# UBC-Thunderbots_PCB_Power__archive_power.net
KiCad netlist of a schematic drawn in Altium Designer
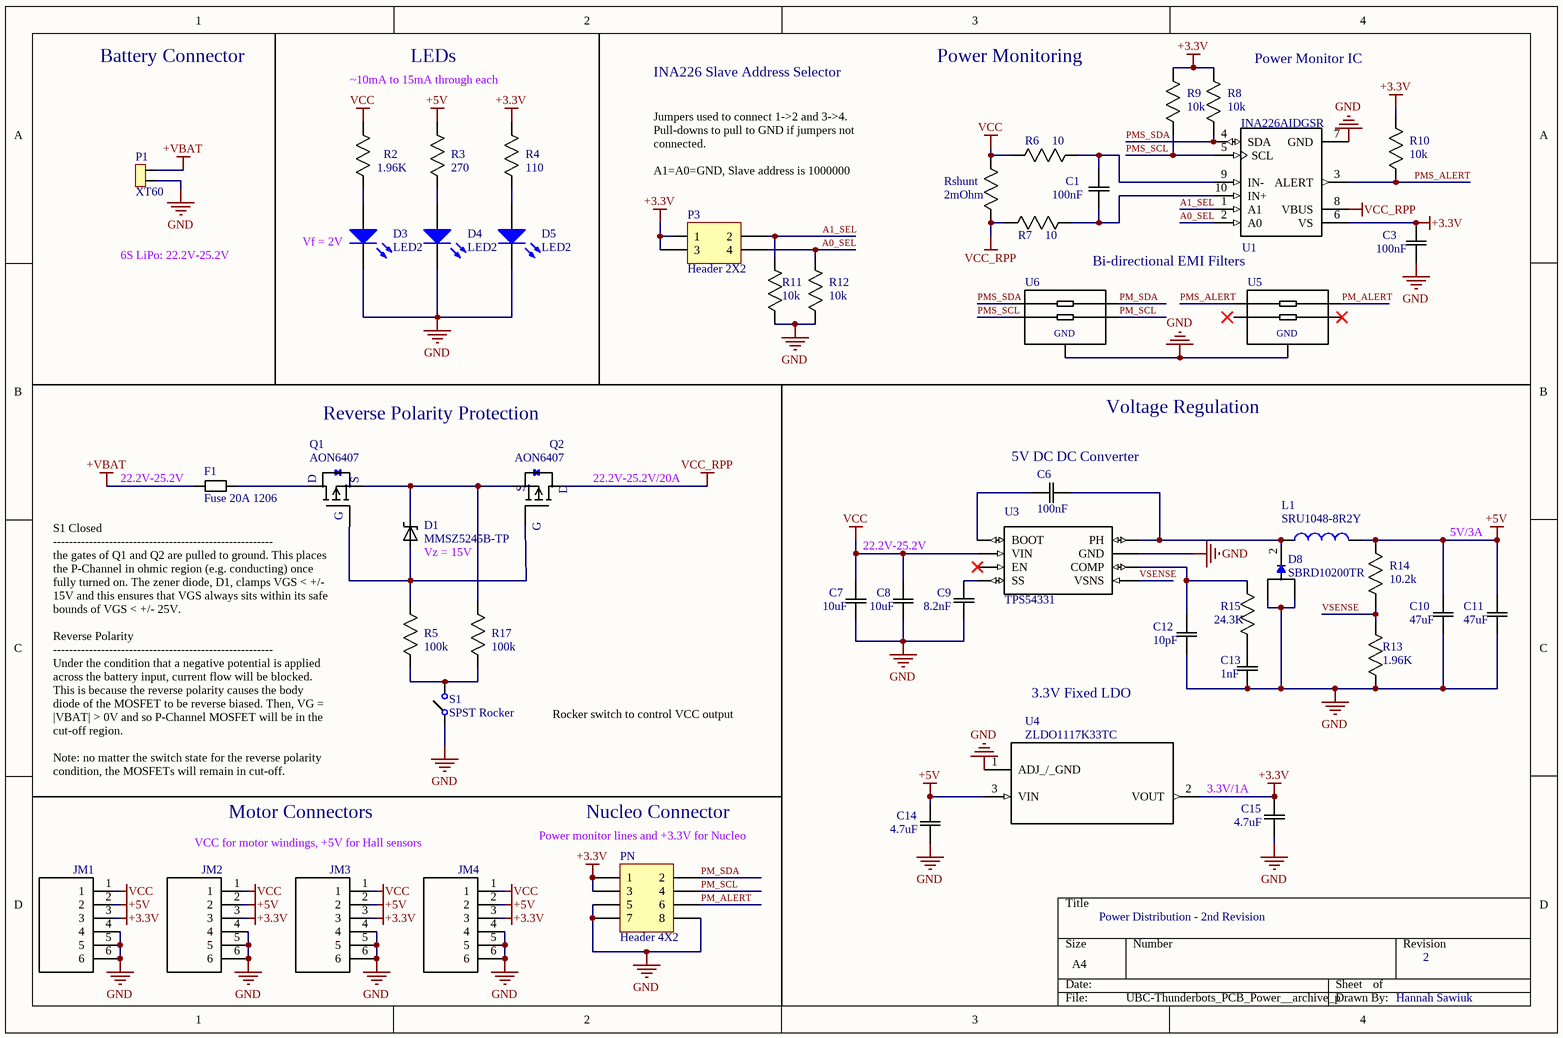
[diagram p0: UBC-Thunderbots_PCB_Power__archive_power-v2.0_pcb__power-v2.0.SchDoc]

(export (version "E")
  (design (tool "Eeschema 10.0.6"))
  (components
    (comp (ref "C1")
      (value "100nF")
      (footprint "0805")
      (description "CAP CER 0.1UF 50V X7R 0805")
      (fields (field (name "MP") "CC0805KRX7R9BB104") (field (name "MF") "Yageo"))
      (libsource (lib "AltiumLibraries") (part "CAP 100nF 0805"))
    )
    (comp (ref "C3")
      (value "100nF")
      (footprint "0805")
      (description "CAP CER 0.1UF 50V X7R 0805")
      (fields (field (name "MP") "CC0805KRX7R9BB104") (field (name "MF") "Yageo"))
      (libsource (lib "AltiumLibraries") (part "CAP 100nF 0805"))
    )
    (comp (ref "C6")
      (value "100nF")
      (footprint "0805")
      (description "CAP CER 0.1UF 50V X7R 0805")
      (fields (field (name "MP") "CC0805KRX7R9BB104") (field (name "MF") "Yageo"))
      (libsource (lib "AltiumLibraries") (part "CAP 100nF 0805"))
    )
    (comp (ref "C7")
      (value "10uF")
      (footprint "1210")
      (description "CAP CER 10UF 50V X7R 1210")
      (fields (field (name "MP") "CL32B106KBJNNWE") (field (name "MF") "Samsung Electro-Mechanics"))
      (libsource (lib "AltiumLibraries") (part "CAP 10uF 1210"))
    )
    (comp (ref "C8")
      (value "10uF")
      (footprint "1210")
      (description "CAP CER 10UF 50V X7R 1210")
      (fields (field (name "MP") "CL32B106KBJNNWE") (field (name "MF") "Samsung Electro-Mechanics"))
      (libsource (lib "AltiumLibraries") (part "CAP 10uF 1210"))
    )
    (comp (ref "C9")
      (value "8.2nF")
      (footprint "0805")
      (description "CAP CER 8200PF 50V X7R 0805")
      (fields (field (name "MP") "C0805C822K5RACTU") (field (name "MF") "KEMET"))
      (libsource (lib "AltiumLibraries") (part "CAP 8.2nF 0805"))
    )
    (comp (ref "C10")
      (value "47uF")
      (footprint "1210")
      (description "CAP CER 47UF 6.3V X7R 1210")
      (fields (field (name "MP") "GCM32ER70J476KE19L") (field (name "MF") "Murata Electronics"))
      (libsource (lib "AltiumLibraries") (part "CAP 47uF 1210"))
    )
    (comp (ref "C11")
      (value "47uF")
      (footprint "1210")
      (description "CAP CER 47UF 6.3V X7R 1210")
      (fields (field (name "MP") "GCM32ER70J476KE19L") (field (name "MF") "Murata Electronics"))
      (libsource (lib "AltiumLibraries") (part "CAP 47uF 1210"))
    )
    (comp (ref "C12")
      (value "10pF")
      (footprint "0603")
      (description "CAP CER SMD 0603 10PF 10% X7R 50")
      (fields (field (name "MP") "C0603C100K5RAC7867") (field (name "MF") "KEMET"))
      (libsource (lib "AltiumLibraries") (part "CAP 10pF 0603"))
    )
    (comp (ref "C13")
      (value "1nF")
      (footprint "0805")
      (description "CAP CER 1000PF 50V X7R 0805")
      (fields (field (name "MP") "CC0805KRX7R9BB102") (field (name "MF") "Yageo"))
      (libsource (lib "AltiumLibraries") (part "CAP 1nF 0805"))
    )
    (comp (ref "C14")
      (value "4.7uF")
      (footprint "0805")
      (description "CAP CER 4.7UF 25V X5R 0805")
      (fields (field (name "MP") "CL21B475KOFNNNE") (field (name "MF") "Samsung Electro-Mechanics"))
      (libsource (lib "AltiumLibraries") (part "CAP 4.7uF 0805"))
    )
    (comp (ref "C15")
      (value "4.7uF")
      (footprint "0805")
      (description "CAP CER 4.7UF 25V X5R 0805")
      (fields (field (name "MP") "CL21B475KOFNNNE") (field (name "MF") "Samsung Electro-Mechanics"))
      (libsource (lib "AltiumLibraries") (part "CAP 4.7uF 0805"))
    )
    (comp (ref "D1")
      (value "MMSZ5245B-TP")
      (footprint "SOD-123")
      (description "Zener Diode 15V 500mW ±5% Surface Mount SOD-123")
      (fields (field (name "MP") "MMSZ5224BT1G") (field (name "MF") "ON Semiconductor"))
      (libsource (lib "AltiumLibraries") (part "MMSZ5245B-TP"))
    )
    (comp (ref "D3")
      (value "LED2")
      (footprint "3.2X1.6X1.1")
      (description "Typical RED, GREEN, YELLOW, AMBER GaAs LED")
      (fields (field (name "MF") "Lite-On Inc.") (field (name "MP") "LTST-C191KGKT"))
      (libsource (lib "AltiumLibraries") (part "LED GREEN SMD"))
    )
    (comp (ref "D4")
      (value "LED2")
      (footprint "3.2X1.6X1.1")
      (description "Typical RED, GREEN, YELLOW, AMBER GaAs LED")
      (fields (field (name "MF") "Lite-On Inc.") (field (name "MP") "LTST-C191KGKT"))
      (libsource (lib "AltiumLibraries") (part "LED GREEN SMD"))
    )
    (comp (ref "D5")
      (value "LED2")
      (footprint "3.2X1.6X1.1")
      (description "Typical RED, GREEN, YELLOW, AMBER GaAs LED")
      (fields (field (name "MF") "Lite-On Inc.") (field (name "MP") "LTST-C191KGKT"))
      (libsource (lib "AltiumLibraries") (part "LED GREEN SMD"))
    )
    (comp (ref "D8")
      (value "SBRD10200TR")
      (footprint "DPAK")
      (description "Diode Schottky 200V 10A Surface Mount DPAK")
      (fields (field (name "MF") "SMC Diode"))
      (libsource (lib "AltiumLibraries") (part "SBRD10200TR"))
    )
    (comp (ref "F1")
      (value "Fuse 20A 1206")
      (footprint "1206")
      (description "FUSE BOARD MOUNT 20A 32VAC 63VDC")
      (fields (field (name "MF") "Schurter Inc.") (field (name "MP") "3413.0331.22"))
      (libsource (lib "AltiumLibraries") (part "Fuse 20A 1206"))
    )
    (comp (ref "JM1")
      (value "CONN HEADER VERT 6POS 3.96MM")
      (footprint "CN HDR 6POS 3.96MM")
      (description "Connector Header Through Hole 6 position 0.156\" (3.96mm)")
      (fields (field (name "MF") "TE Connectivity") (field (name "MP") "1877285-6"))
      (libsource (lib "AltiumLibraries") (part "CONN HEADER VERT 6POS 3.96MM"))
    )
    (comp (ref "JM2")
      (value "CONN HEADER VERT 6POS 3.96MM")
      (footprint "CN HDR 6POS 3.96MM")
      (description "Connector Header Through Hole 6 position 0.156\" (3.96mm)")
      (fields (field (name "MF") "TE Connectivity") (field (name "MP") "1877285-6"))
      (libsource (lib "AltiumLibraries") (part "CONN HEADER VERT 6POS 3.96MM"))
    )
    (comp (ref "JM3")
      (value "CONN HEADER VERT 6POS 3.96MM")
      (footprint "CN HDR 6POS 3.96MM")
      (description "Connector Header Through Hole 6 position 0.156\" (3.96mm)")
      (fields (field (name "MF") "TE Connectivity") (field (name "MP") "1877285-6"))
      (libsource (lib "AltiumLibraries") (part "CONN HEADER VERT 6POS 3.96MM"))
    )
    (comp (ref "JM4")
      (value "CONN HEADER VERT 6POS 3.96MM")
      (footprint "CN HDR 6POS 3.96MM")
      (description "Connector Header Through Hole 6 position 0.156\" (3.96mm)")
      (fields (field (name "MF") "TE Connectivity") (field (name "MP") "1877285-6"))
      (libsource (lib "AltiumLibraries") (part "CONN HEADER VERT 6POS 3.96MM"))
    )
    (comp (ref "L1")
      (value "SRU1048-8R2Y")
      (footprint "Inductor")
      (description "FIXED IND 8.2UH 4.6A 15 MOHM SMD")
      (fields (field (name "MF") "Bourns Inc."))
      (libsource (lib "AltiumLibraries") (part "SRU1048-8R2Y"))
    )
    (comp (ref "P1")
      (value "XT60")
      (footprint "XT60Connector")
      (description "XT60 CONNECTORS FEMALE PAIR")
      (fields (field (name "MF") "SparkFun Electronics") (field (name "MP") "PRT-10474"))
      (libsource (lib "AltiumLibraries") (part "XT60 Connector"))
    )
    (comp (ref "P3")
      (value "Header 2X2")
      (footprint "HDR2X2")
      (description "Header, 2-Pin, Dual row")
      (fields (field (name "PUBLISHER") "Altium Limited"))
      (libsource (lib "Miscellaneous Connectors") (part "Header 2X2"))
    )
    (comp (ref "PN")
      (value "Header 4X2")
      (footprint "HDR2X4")
      (description "Header, 4-Pin, Dual row")
      (fields (field (name "PUBLISHER") "Altium Limited"))
      (libsource (lib "Miscellaneous Connectors") (part "Header 4X2"))
    )
    (comp (ref "Q1")
      (value "AON6407")
      (footprint "8-PowerSMD")
      (description "P-Channel 30V 32A (Ta), 85A (Tc) 7.3W (Ta), 83W (Tc) Surface Mount 8-DFN (5x6)")
      (fields (field (name "MF") "Alpha & Omega Semiconductor Inc."))
      (libsource (lib "AltiumLibraries") (part "AON6407"))
    )
    (comp (ref "Q2")
      (value "AON6407")
      (footprint "8-PowerSMD")
      (description "P-Channel 30V 32A (Ta), 85A (Tc) 7.3W (Ta), 83W (Tc) Surface Mount 8-DFN (5x6)")
      (fields (field (name "MF") "Alpha & Omega Semiconductor Inc."))
      (libsource (lib "AltiumLibraries") (part "AON6407"))
    )
    (comp (ref "R2")
      (value "1.96K")
      (footprint "0805")
      (description "RES SMD 1.96K OHM 1% 1/8W 0805")
      (fields (field (name "MP") "ERJ-6ENF1961V") (field (name "MF") "Panasonic Electronic Components"))
      (libsource (lib "AltiumLibraries") (part "RES 1.96k 0805"))
    )
    (comp (ref "R3")
      (value "270")
      (footprint "0805")
      (description "RES SMD 270 OHM 5% 1/8W 0805")
      (fields (field (name "MP") "RC0805JR-07270RL") (field (name "MF") "Yageo"))
      (libsource (lib "AltiumLibraries") (part "RES 270 0805"))
    )
    (comp (ref "R4")
      (value "110")
      (footprint "0805")
      (description "RES SMD 110 OHM 1% 1/8W 0805")
      (fields (field (name "MP") "RC0805FR-07110RL") (field (name "MF") "Yageo"))
      (libsource (lib "AltiumLibraries") (part "RES 110 0805"))
    )
    (comp (ref "R5")
      (value "100k")
      (footprint "0805")
      (description "RES SMD 100K OHM 1% 1/8W 0805")
      (fields (field (name "MP") "RC0805FR-07100KL") (field (name "MF") "Yageo"))
      (libsource (lib "AltiumLibraries") (part "RES 100k 0805"))
    )
    (comp (ref "R6")
      (value "10")
      (footprint "0805")
      (description "RES SMD 10 OHM 1% 1/8W 0805")
      (fields (field (name "MP") "RC0805FR-0710RL") (field (name "MF") "Yageo"))
      (libsource (lib "AltiumLibraries") (part "RES 10 0805"))
    )
    (comp (ref "R7")
      (value "10")
      (footprint "0805")
      (description "RES SMD 10 OHM 1% 1/8W 0805")
      (fields (field (name "MP") "RC0805FR-0710RL") (field (name "MF") "Yageo"))
      (libsource (lib "AltiumLibraries") (part "RES 10 0805"))
    )
    (comp (ref "R8")
      (value "10k")
      (footprint "0805")
      (description "RES SMD 10K OHM 1% 1/8W 0805")
      (fields (field (name "MP") "RC0805FR-0710KL") (field (name "MF") "Yageo"))
      (libsource (lib "AltiumLibraries") (part "RES 10k 0805"))
    )
    (comp (ref "R9")
      (value "10k")
      (footprint "0805")
      (description "RES SMD 10K OHM 1% 1/8W 0805")
      (fields (field (name "MP") "RC0805FR-0710KL") (field (name "MF") "Yageo"))
      (libsource (lib "AltiumLibraries") (part "RES 10k 0805"))
    )
    (comp (ref "R10")
      (value "10k")
      (footprint "0805")
      (description "RES SMD 10K OHM 1% 1/8W 0805")
      (fields (field (name "MP") "RC0805FR-0710KL") (field (name "MF") "Yageo"))
      (libsource (lib "AltiumLibraries") (part "RES 10k 0805"))
    )
    (comp (ref "R11")
      (value "10k")
      (footprint "0805")
      (description "RES SMD 10K OHM 1% 1/8W 0805")
      (fields (field (name "MP") "RC0805FR-0710KL") (field (name "MF") "Yageo"))
      (libsource (lib "AltiumLibraries") (part "RES 10k 0805"))
    )
    (comp (ref "R12")
      (value "10k")
      (footprint "0805")
      (description "RES SMD 10K OHM 1% 1/8W 0805")
      (fields (field (name "MP") "RC0805FR-0710KL") (field (name "MF") "Yageo"))
      (libsource (lib "AltiumLibraries") (part "RES 10k 0805"))
    )
    (comp (ref "R13")
      (value "1.96K")
      (footprint "0805")
      (description "RES SMD 1.96K OHM 1% 1/8W 0805")
      (fields (field (name "MP") "ERJ-6ENF1961V") (field (name "MF") "Panasonic Electronic Components"))
      (libsource (lib "AltiumLibraries") (part "RES 1.96k 0805"))
    )
    (comp (ref "R14")
      (value "10.2k")
      (footprint "0805")
      (description "RES SMD 10.2K OHM 1% 1/8W 0805")
      (fields (field (name "MP") "ERJ-6ENF1022V") (field (name "MF") "Panasonic Electronic Components"))
      (libsource (lib "AltiumLibraries") (part "RES 10.2k 0805"))
    )
    (comp (ref "R15")
      (value "24.3K")
      (footprint "0805")
      (description "RES SMD 24.3K OHM 1% 1/8W 0805")
      (fields (field (name "MP") "RC0805FR-0724K3L") (field (name "MF") "Yageo"))
      (libsource (lib "AltiumLibraries") (part "RES 24.3k 0805"))
    )
    (comp (ref "R17")
      (value "100k")
      (footprint "0805")
      (description "RES SMD 100K OHM 1% 1/8W 0805")
      (fields (field (name "MP") "RC0805FR-07100KL") (field (name "MF") "Yageo"))
      (libsource (lib "AltiumLibraries") (part "RES 100k 0805"))
    )
    (comp (ref "Rshunt")
      (value "2mOhm")
      (footprint "1206")
      (description "RES 0.002 OHM 1% 1W 1206")
      (fields (field (name "MP") "CSR1206-0R002F1") (field (name "MF") "Riedon"))
      (libsource (lib "AltiumLibraries") (part "RES 2mOhm 1206"))
    )
    (comp (ref "S1")
      (value "SPST Rocker")
      (footprint "SWITCH ROCKER SPST 10A 125V")
      (description "Rocker Switch SPST 10A (AC) 125V Panel Mount, Snap-In")
      (fields (field (name "MP") "SRB22A2FBBNN") (field (name "MF") "ZF Electronics"))
      (libsource (lib "AltiumLibraries") (part "SWITCH ROCKER SPST 10A 125V"))
    )
    (comp (ref "U1")
      (value "INA226AIDGSR")
      (footprint "10-VSSOP")
      (fields (field (name "MF") "Texas Instruments"))
      (libsource (lib "AltiumLibraries") (part "INA226AIDGSR"))
    )
    (comp (ref "U3")
      (value "TPS54331")
      (footprint "8-PowerSOIC")
      (description "Buck Switching Regulator IC Positive Adjustable 0.8V 1 Output 3A 8-SOIC _0.154, 3.90mm Width_")
      (fields (field (name "MP") "TPS54331DDAR") (field (name "MF") "Texas Instruments"))
      (libsource (lib "AltiumLibraries") (part "TPS54331"))
    )
    (comp (ref "U4")
      (value "ZLDO1117K33TC")
      (footprint "TO-252-3")
      (description "Linear Voltage Regulator IC Positive Fixed 1 Output  1A TO-252-3")
      (fields (field (name "MF") "Diodes Incorporated"))
      (libsource (lib "AltiumLibraries") (part "ZLDO1117K33TC"))
    )
    (comp (ref "U5")
      (value "EMI")
      (footprint "SOT-665")
      (description "RC (Pi) EMI Filter 2nd Order Low Pass 2 Channel R = 100Ohms, C = 19pF (Total)  SOT-665")
      (fields (field (name "MF") "Nexperia USA Inc.") (field (name "MP") "IP4256CZ5-W,115"))
      (libsource (lib "AltiumLibraries") (part "IP4256CZ5-W"))
    )
    (comp (ref "U6")
      (value "EMI")
      (footprint "SOT-665")
      (description "RC (Pi) EMI Filter 2nd Order Low Pass 2 Channel R = 100Ohms, C = 19pF (Total)  SOT-665")
      (fields (field (name "MF") "Nexperia USA Inc.") (field (name "MP") "IP4256CZ5-W,115"))
      (libsource (lib "AltiumLibraries") (part "IP4256CZ5-W"))
    )
  )
  (nets
    (net (code "1") (name "+3.3V") (class "Default")
      (node (ref "C15") (pin "2") (pinfunction "C2_2") (pintype "passive"))
      (node (ref "C3") (pin "2") (pinfunction "C2_2") (pintype "passive"))
      (node (ref "JM1") (pin "3") (pinfunction "3_3") (pintype "passive"))
      (node (ref "JM2") (pin "3") (pinfunction "3_3") (pintype "passive"))
      (node (ref "JM3") (pin "3") (pinfunction "3_3") (pintype "passive"))
      (node (ref "JM4") (pin "3") (pinfunction "3_3") (pintype "passive"))
      (node (ref "P3") (pin "1") (pinfunction "1_1") (pintype "passive"))
      (node (ref "P3") (pin "3") (pinfunction "3_3") (pintype "passive"))
      (node (ref "PN") (pin "1") (pinfunction "1_1") (pintype "passive"))
      (node (ref "PN") (pin "3") (pinfunction "3_3") (pintype "passive"))
      (node (ref "R10") (pin "1") (pinfunction "R1_1") (pintype "passive"))
      (node (ref "R4") (pin "1") (pinfunction "R1_1") (pintype "passive"))
      (node (ref "R8") (pin "1") (pinfunction "R1_1") (pintype "passive"))
      (node (ref "R9") (pin "1") (pinfunction "R1_1") (pintype "passive"))
      (node (ref "U1") (pin "6") (pinfunction "VS_6") (pintype "power_in"))
      (node (ref "U4") (pin "2") (pinfunction "VOUT_2") (pintype "output"))
    )
    (net (code "2") (name "+5V") (class "Default")
      (node (ref "C10") (pin "2") (pinfunction "C2_2") (pintype "passive"))
      (node (ref "C11") (pin "2") (pinfunction "C2_2") (pintype "passive"))
      (node (ref "C14") (pin "2") (pinfunction "C2_2") (pintype "passive"))
      (node (ref "JM1") (pin "2") (pinfunction "2_2") (pintype "passive"))
      (node (ref "JM2") (pin "2") (pinfunction "2_2") (pintype "passive"))
      (node (ref "JM3") (pin "2") (pinfunction "2_2") (pintype "passive"))
      (node (ref "JM4") (pin "2") (pinfunction "2_2") (pintype "passive"))
      (node (ref "L1") (pin "2") (pinfunction "2_2") (pintype "passive"))
      (node (ref "R14") (pin "1") (pinfunction "R1_1") (pintype "passive"))
      (node (ref "R3") (pin "1") (pinfunction "R1_1") (pintype "passive"))
      (node (ref "U4") (pin "3") (pinfunction "VIN_3") (pintype "input"))
    )
    (net (code "3") (name "+VBAT") (class "Default")
      (node (ref "F1") (pin "1") (pinfunction "1_1") (pintype "passive"))
      (node (ref "P1") (pin "2") (pinfunction "2_2") (pintype "passive"))
    )
    (net (code "4") (name "/A0_SEL") (class "Default")
      (node (ref "P3") (pin "4") (pinfunction "4_4") (pintype "passive"))
      (node (ref "R12") (pin "1") (pinfunction "R1_1") (pintype "passive"))
      (node (ref "U1") (pin "2") (pinfunction "A0_2") (pintype "input"))
    )
    (net (code "5") (name "/A1_SEL") (class "Default")
      (node (ref "P3") (pin "2") (pinfunction "2_2") (pintype "passive"))
      (node (ref "R11") (pin "1") (pinfunction "R1_1") (pintype "passive"))
      (node (ref "U1") (pin "1") (pinfunction "A1_1") (pintype "input"))
    )
    (net (code "6") (name "/PMS_ALERT") (class "Default")
      (node (ref "R10") (pin "2") (pinfunction "R2_2") (pintype "passive"))
      (node (ref "U1") (pin "3") (pinfunction "ALERT_3") (pintype "output"))
      (node (ref "U5") (pin "1") (pinfunction "P$1_1") (pintype "passive"))
    )
    (net (code "7") (name "/PMS_SCL") (class "Default")
      (node (ref "R9") (pin "2") (pinfunction "R2_2") (pintype "passive"))
      (node (ref "U1") (pin "5") (pinfunction "SCL_5") (pintype "input"))
      (node (ref "U6") (pin "3") (pinfunction "P$3_3") (pintype "passive"))
    )
    (net (code "8") (name "/PMS_SDA") (class "Default")
      (node (ref "R8") (pin "2") (pinfunction "R2_2") (pintype "passive"))
      (node (ref "U1") (pin "4") (pinfunction "SDA_4") (pintype "bidirectional"))
      (node (ref "U6") (pin "1") (pinfunction "P$1_1") (pintype "passive"))
    )
    (net (code "9") (name "/PM_ALERT") (class "Default")
      (node (ref "PN") (pin "6") (pinfunction "6_6") (pintype "passive"))
      (node (ref "U5") (pin "5") (pinfunction "P$5_5") (pintype "passive"))
    )
    (net (code "10") (name "/PM_SCL") (class "Default")
      (node (ref "PN") (pin "4") (pinfunction "4_4") (pintype "passive"))
      (node (ref "U6") (pin "4") (pinfunction "P$4_4") (pintype "passive"))
    )
    (net (code "11") (name "/PM_SDA") (class "Default")
      (node (ref "PN") (pin "2") (pinfunction "2_2") (pintype "passive"))
      (node (ref "U6") (pin "5") (pinfunction "P$5_5") (pintype "passive"))
    )
    (net (code "12") (name "/VSENSE") (class "Default")
      (node (ref "R13") (pin "1") (pinfunction "R1_1") (pintype "passive"))
      (node (ref "R14") (pin "2") (pinfunction "R2_2") (pintype "passive"))
      (node (ref "U3") (pin "5") (pinfunction "VSNS_5") (pintype "input"))
    )
    (net (code "13") (name "GND") (class "Default")
      (node (ref "C10") (pin "1") (pinfunction "C1_1") (pintype "passive"))
      (node (ref "C11") (pin "1") (pinfunction "C1_1") (pintype "passive"))
      (node (ref "C12") (pin "1") (pinfunction "C1_1") (pintype "passive"))
      (node (ref "C13") (pin "1") (pinfunction "C1_1") (pintype "passive"))
      (node (ref "C14") (pin "1") (pinfunction "C1_1") (pintype "passive"))
      (node (ref "C15") (pin "1") (pinfunction "C1_1") (pintype "passive"))
      (node (ref "C3") (pin "1") (pinfunction "C1_1") (pintype "passive"))
      (node (ref "C7") (pin "1") (pinfunction "C1_1") (pintype "passive"))
      (node (ref "C8") (pin "1") (pinfunction "C1_1") (pintype "passive"))
      (node (ref "C9") (pin "2") (pinfunction "C2_2") (pintype "passive"))
      (node (ref "D3") (pin "2") (pinfunction "K_2") (pintype "passive"))
      (node (ref "D4") (pin "2") (pinfunction "K_2") (pintype "passive"))
      (node (ref "D5") (pin "2") (pinfunction "K_2") (pintype "passive"))
      (node (ref "D8") (pin "1") (pinfunction "1_1") (pintype "passive"))
      (node (ref "D8") (pin "3") (pinfunction "3_3") (pintype "passive"))
      (node (ref "JM1") (pin "4") (pinfunction "4_4") (pintype "passive"))
      (node (ref "JM1") (pin "5") (pinfunction "5_5") (pintype "passive"))
      (node (ref "JM1") (pin "6") (pinfunction "6_6") (pintype "passive"))
      (node (ref "JM2") (pin "4") (pinfunction "4_4") (pintype "passive"))
      (node (ref "JM2") (pin "5") (pinfunction "5_5") (pintype "passive"))
      (node (ref "JM2") (pin "6") (pinfunction "6_6") (pintype "passive"))
      (node (ref "JM3") (pin "4") (pinfunction "4_4") (pintype "passive"))
      (node (ref "JM3") (pin "5") (pinfunction "5_5") (pintype "passive"))
      (node (ref "JM3") (pin "6") (pinfunction "6_6") (pintype "passive"))
      (node (ref "JM4") (pin "4") (pinfunction "4_4") (pintype "passive"))
      (node (ref "JM4") (pin "5") (pinfunction "5_5") (pintype "passive"))
      (node (ref "JM4") (pin "6") (pinfunction "6_6") (pintype "passive"))
      (node (ref "P1") (pin "1") (pinfunction "1_1") (pintype "passive"))
      (node (ref "PN") (pin "5") (pinfunction "5_5") (pintype "passive"))
      (node (ref "PN") (pin "7") (pinfunction "7_7") (pintype "passive"))
      (node (ref "PN") (pin "8") (pinfunction "8_8") (pintype "passive"))
      (node (ref "R11") (pin "2") (pinfunction "R2_2") (pintype "passive"))
      (node (ref "R12") (pin "2") (pinfunction "R2_2") (pintype "passive"))
      (node (ref "R13") (pin "2") (pinfunction "R2_2") (pintype "passive"))
      (node (ref "S1") (pin "0") (pinfunction "0_0") (pintype "passive"))
      (node (ref "U1") (pin "7") (pinfunction "GND_7") (pintype "power_in"))
      (node (ref "U3") (pin "7") (pinfunction "GND_7") (pintype "power_in"))
      (node (ref "U4") (pin "1") (pinfunction "ADJ_/_GND_1") (pintype "power_in"))
      (node (ref "U5") (pin "2") (pinfunction "P$2_2") (pintype "passive"))
      (node (ref "U6") (pin "2") (pinfunction "P$2_2") (pintype "passive"))
    )
    (net (code "14") (name "Net-(C1-C1)") (class "Default")
      (node (ref "C1") (pin "1") (pinfunction "C1_1") (pintype "passive"))
      (node (ref "R7") (pin "1") (pinfunction "R1_1") (pintype "passive"))
      (node (ref "U1") (pin "10") (pinfunction "IN+_10") (pintype "input"))
    )
    (net (code "15") (name "Net-(C1-C2)") (class "Default")
      (node (ref "C1") (pin "2") (pinfunction "C2_2") (pintype "passive"))
      (node (ref "R6") (pin "1") (pinfunction "R1_1") (pintype "passive"))
      (node (ref "U1") (pin "9") (pinfunction "IN-_9") (pintype "input"))
    )
    (net (code "16") (name "Net-(C6-C1)") (class "Default")
      (node (ref "C6") (pin "1") (pinfunction "C1_1") (pintype "passive"))
      (node (ref "U3") (pin "1") (pinfunction "BOOT_1") (pintype "bidirectional"))
    )
    (net (code "17") (name "Net-(C6-C2)") (class "Default")
      (node (ref "C6") (pin "2") (pinfunction "C2_2") (pintype "passive"))
      (node (ref "D8") (pin "2") (pinfunction "2_2") (pintype "passive"))
      (node (ref "L1") (pin "1") (pinfunction "1_1") (pintype "passive"))
      (node (ref "U3") (pin "8") (pinfunction "PH_8") (pintype "bidirectional"))
    )
    (net (code "18") (name "Net-(C9-C1)") (class "Default")
      (node (ref "C9") (pin "1") (pinfunction "C1_1") (pintype "passive"))
      (node (ref "U3") (pin "4") (pinfunction "SS_4") (pintype "bidirectional"))
    )
    (net (code "19") (name "Net-(C12-C2)") (class "Default")
      (node (ref "C12") (pin "2") (pinfunction "C2_2") (pintype "passive"))
      (node (ref "R15") (pin "1") (pinfunction "R1_1") (pintype "passive"))
      (node (ref "U3") (pin "6") (pinfunction "COMP_6") (pintype "bidirectional"))
    )
    (net (code "20") (name "Net-(C13-C2)") (class "Default")
      (node (ref "C13") (pin "2") (pinfunction "C2_2") (pintype "passive"))
      (node (ref "R15") (pin "2") (pinfunction "R2_2") (pintype "passive"))
    )
    (net (code "21") (name "Net-(D3-A)") (class "Default")
      (node (ref "D3") (pin "1") (pinfunction "A_1") (pintype "passive"))
      (node (ref "R2") (pin "2") (pinfunction "R2_2") (pintype "passive"))
    )
    (net (code "22") (name "Net-(D4-A)") (class "Default")
      (node (ref "D4") (pin "1") (pinfunction "A_1") (pintype "passive"))
      (node (ref "R3") (pin "2") (pinfunction "R2_2") (pintype "passive"))
    )
    (net (code "23") (name "Net-(D5-A)") (class "Default")
      (node (ref "D5") (pin "1") (pinfunction "A_1") (pintype "passive"))
      (node (ref "R4") (pin "2") (pinfunction "R2_2") (pintype "passive"))
    )
    (net (code "24") (name "Net-(F1-Pad2)") (class "Default")
      (node (ref "F1") (pin "2") (pinfunction "2_2") (pintype "passive"))
      (node (ref "Q1") (pin "D") (pinfunction "D_D") (pintype "passive"))
    )
    (net (code "25") (name "Net-(R5-R1)") (class "Default")
      (node (ref "D1") (pin "A") (pinfunction "A_A") (pintype "passive"))
      (node (ref "Q1") (pin "G") (pinfunction "G_G") (pintype "passive"))
      (node (ref "Q2") (pin "G") (pinfunction "G_G") (pintype "passive"))
      (node (ref "R5") (pin "1") (pinfunction "R1_1") (pintype "passive"))
    )
    (net (code "26") (name "Net-(R17-R1)") (class "Default")
      (node (ref "D1") (pin "C") (pinfunction "C_C") (pintype "passive"))
      (node (ref "Q1") (pin "S") (pinfunction "S_S") (pintype "passive"))
      (node (ref "Q2") (pin "S") (pinfunction "S_S") (pintype "passive"))
      (node (ref "R17") (pin "1") (pinfunction "R1_1") (pintype "passive"))
    )
    (net (code "27") (name "Net-(R17-R2)") (class "Default")
      (node (ref "R17") (pin "2") (pinfunction "R2_2") (pintype "passive"))
      (node (ref "R5") (pin "2") (pinfunction "R2_2") (pintype "passive"))
      (node (ref "S1") (pin "1") (pinfunction "1_1") (pintype "passive"))
    )
    (net (code "28") (name "PowerPAD") (class "Default")
      (node (ref "U3") (pin "9") (pinfunction "PowerPAD_9") (pintype "power_in"))
    )
    (net (code "29") (name "VCC") (class "Default")
      (node (ref "C7") (pin "2") (pinfunction "C2_2") (pintype "passive"))
      (node (ref "C8") (pin "2") (pinfunction "C2_2") (pintype "passive"))
      (node (ref "JM1") (pin "1") (pinfunction "1_1") (pintype "passive"))
      (node (ref "JM2") (pin "1") (pinfunction "1_1") (pintype "passive"))
      (node (ref "JM3") (pin "1") (pinfunction "1_1") (pintype "passive"))
      (node (ref "JM4") (pin "1") (pinfunction "1_1") (pintype "passive"))
      (node (ref "R2") (pin "1") (pinfunction "R1_1") (pintype "passive"))
      (node (ref "R6") (pin "2") (pinfunction "R2_2") (pintype "passive"))
      (node (ref "Rshunt") (pin "1") (pinfunction "R1_1") (pintype "passive"))
      (node (ref "U3") (pin "2") (pinfunction "VIN_2") (pintype "input"))
    )
    (net (code "30") (name "VCC_RPP") (class "Default")
      (node (ref "Q2") (pin "D") (pinfunction "D_D") (pintype "passive"))
      (node (ref "R7") (pin "2") (pinfunction "R2_2") (pintype "passive"))
      (node (ref "Rshunt") (pin "2") (pinfunction "R2_2") (pintype "passive"))
      (node (ref "U1") (pin "8") (pinfunction "VBUS_8") (pintype "power_in"))
    )
    (net (code "31") (name "unconnected-(U3-EN-Pad3)") (class "Default")
      (node (ref "U3") (pin "3") (pinfunction "EN_3") (pintype "input+no_connect"))
    )
    (net (code "32") (name "unconnected-(U5-P$3-Pad3)") (class "Default")
      (node (ref "U5") (pin "3") (pinfunction "P$3_3") (pintype "passive"))
    )
    (net (code "33") (name "unconnected-(U5-P$4-Pad4)") (class "Default")
      (node (ref "U5") (pin "4") (pinfunction "P$4_4") (pintype "passive+no_connect"))
    )
  )
)
